# camera.net
KiCad netlist of a schematic drawn in Altium Designer
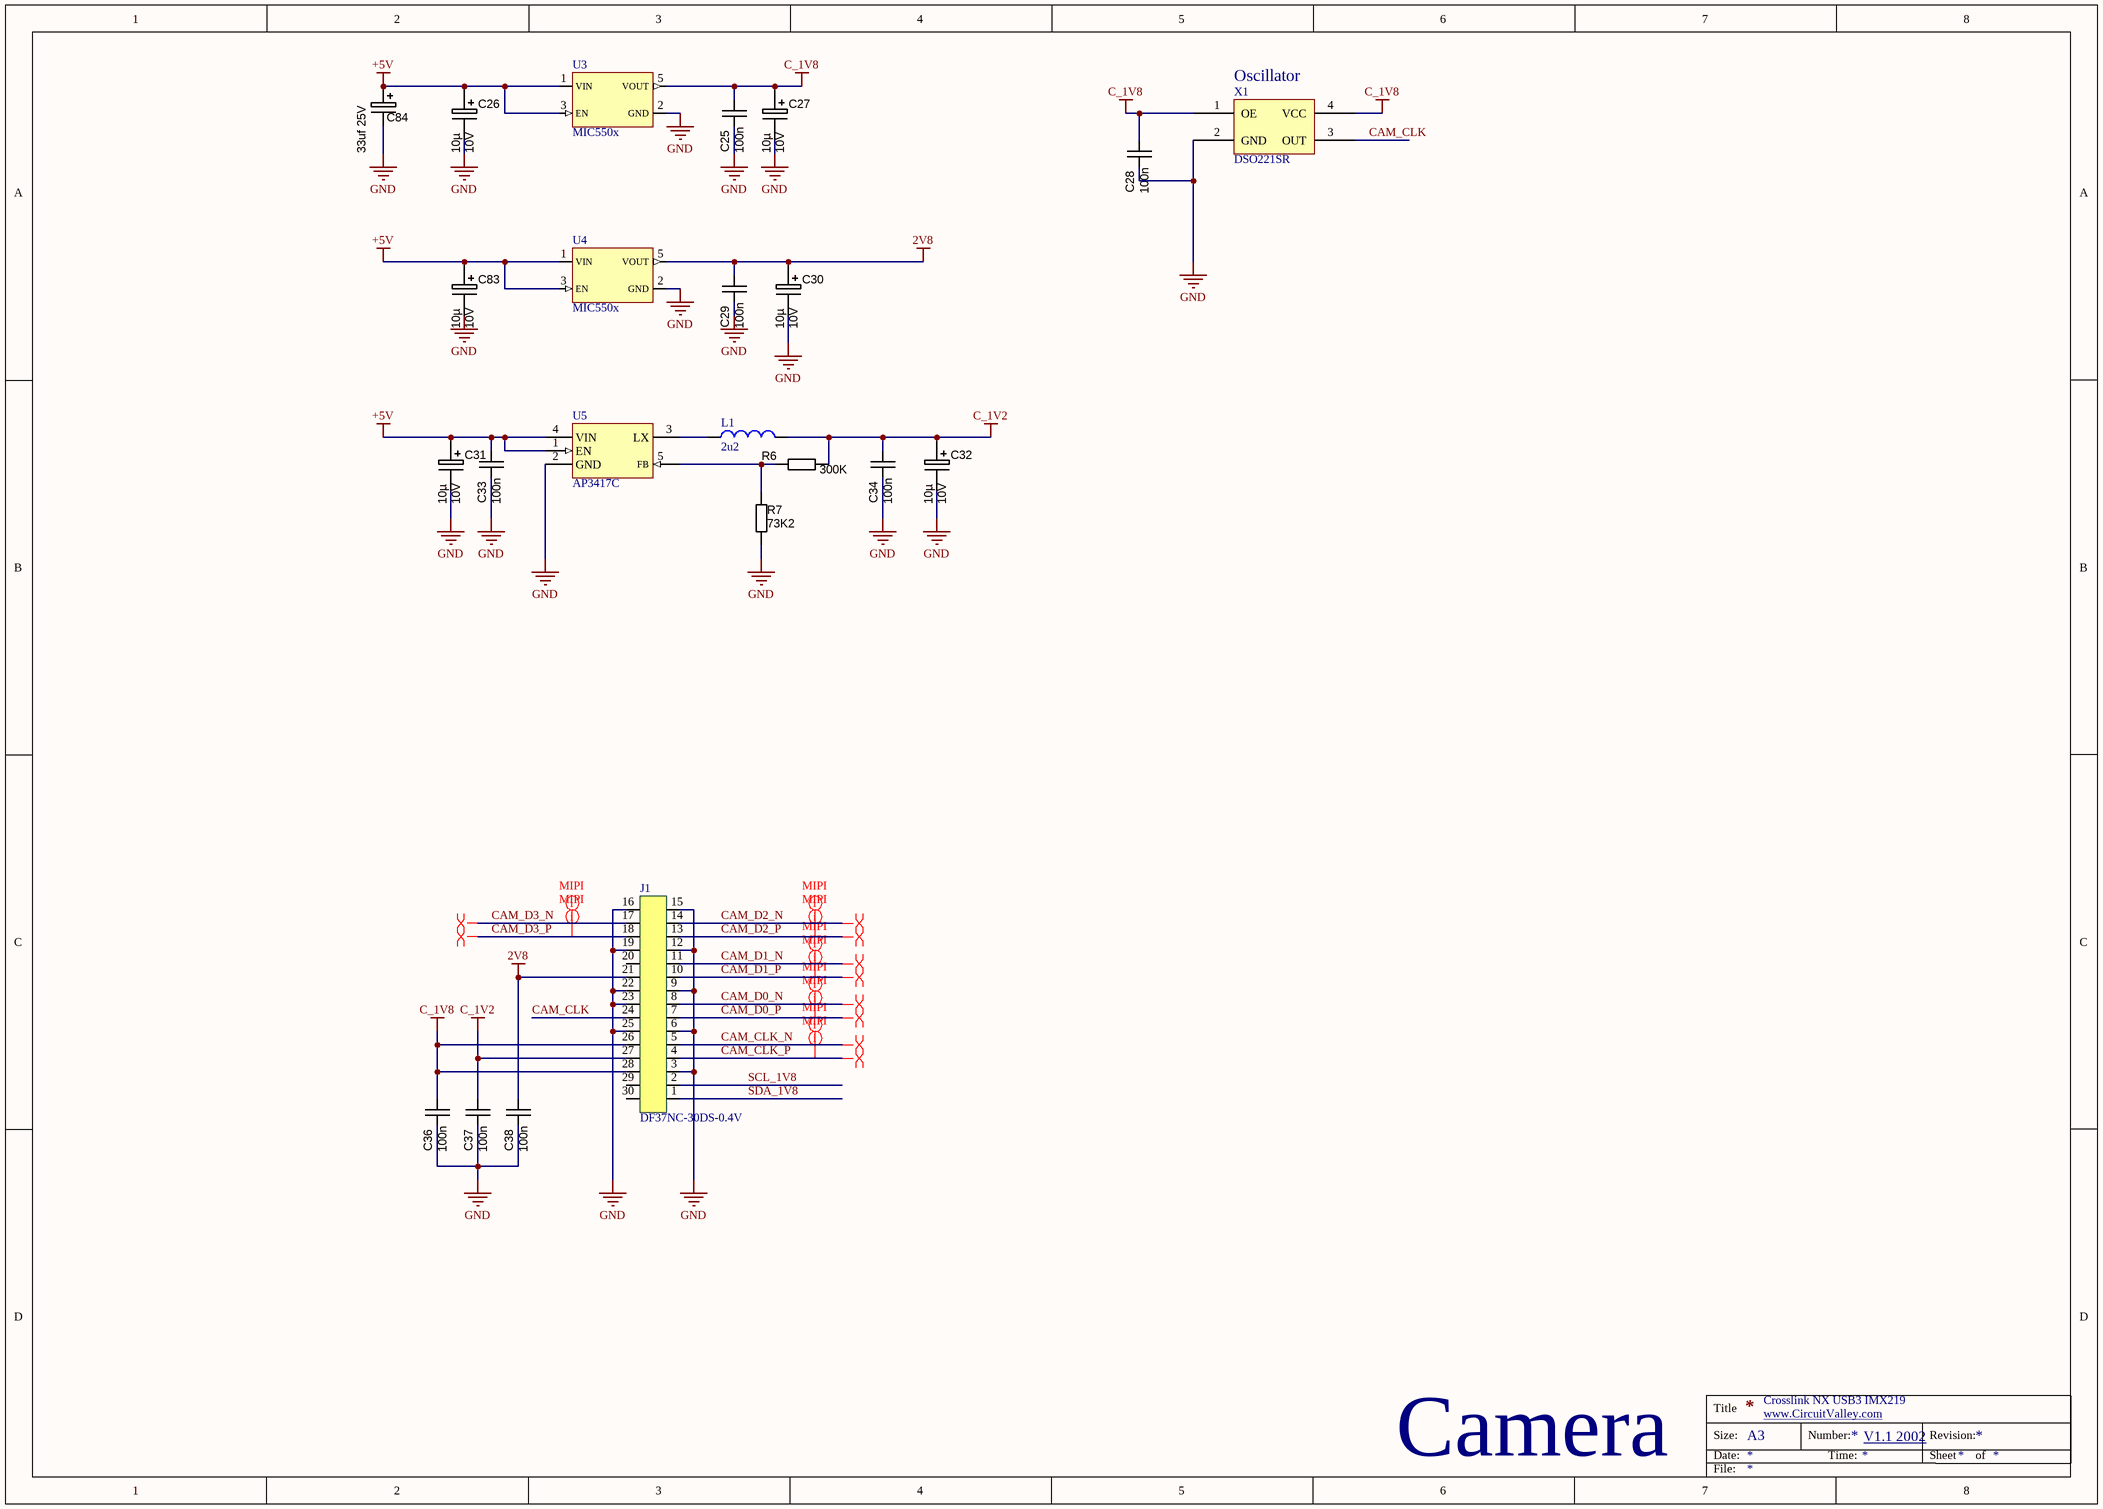
[diagram p0: camera.SchDoc]

(export (version "E")
  (design (tool "Eeschema 10.0.6"))
  (components
    (comp (ref "C25")
      (value "100n")
      (footprint "CAPC1608N")
      (description "Capacitor SMD Cer 10pF 5% 50V NP0 0603")
      (fields (field (name "TOLERANCE") "±5%") (field (name "PART") "C0603X104K5RAC"))
      (libsource (lib "PBL - Capacitors") (part "CAPC_10p_0603_NP0_1%_50V"))
    )
    (comp (ref "C26")
      (value "10µ")
      (footprint "CAPMP3528X210N")
      (description "Capacitor SMD Tantalum 47uF 20% 6.3V 1210")
      (fields (field (name "TOLERANCE") "±20%") (field (name "RATINGS") "10V"))
      (libsource (lib "PBL - Capacitors") (part "CAPT_47u_1210_6V3"))
    )
    (comp (ref "C27")
      (value "10µ")
      (footprint "CAPMP3528X210N")
      (description "Capacitor SMD Tantalum 47uF 20% 6.3V 1210")
      (fields (field (name "TOLERANCE") "±20%") (field (name "RATINGS") "10V"))
      (libsource (lib "PBL - Capacitors") (part "CAPT_47u_1210_6V3"))
    )
    (comp (ref "C28")
      (value "100n")
      (footprint "CAPC1608N")
      (description "Capacitor SMD Cer 10pF 5% 50V NP0 0603")
      (fields (field (name "TOLERANCE") "±5%") (field (name "PART") "C0603X104K5RAC"))
      (libsource (lib "PBL - Capacitors") (part "CAPC_10p_0603_NP0_1%_50V"))
    )
    (comp (ref "C29")
      (value "100n")
      (footprint "CAPC1608N")
      (description "Capacitor SMD Cer 10pF 5% 50V NP0 0603")
      (fields (field (name "TOLERANCE") "±5%") (field (name "PART") "C0603X104K5RAC"))
      (libsource (lib "PBL - Capacitors") (part "CAPC_10p_0603_NP0_1%_50V"))
    )
    (comp (ref "C30")
      (value "10µ")
      (footprint "CAPMP3528X210N")
      (description "Capacitor SMD Tantalum 47uF 20% 6.3V 1210")
      (fields (field (name "TOLERANCE") "±20%") (field (name "RATINGS") "10V"))
      (libsource (lib "PBL - Capacitors") (part "CAPT_47u_1210_6V3"))
    )
    (comp (ref "C31")
      (value "10µ")
      (footprint "CAPMP3528X210N")
      (description "Capacitor SMD Tantalum 47uF 20% 6.3V 1210")
      (fields (field (name "TOLERANCE") "±20%") (field (name "RATINGS") "10V"))
      (libsource (lib "PBL - Capacitors") (part "CAPT_47u_1210_6V3"))
    )
    (comp (ref "C32")
      (value "10µ")
      (footprint "CAPMP3528X210N")
      (description "Capacitor SMD Tantalum 47uF 20% 6.3V 1210")
      (fields (field (name "TOLERANCE") "±20%") (field (name "RATINGS") "10V"))
      (libsource (lib "PBL - Capacitors") (part "CAPT_47u_1210_6V3"))
    )
    (comp (ref "C33")
      (value "100n")
      (footprint "CAPC1608N")
      (description "Capacitor SMD Cer 10pF 5% 50V NP0 0603")
      (fields (field (name "TOLERANCE") "±5%") (field (name "PART") "C0603X104K5RAC"))
      (libsource (lib "PBL - Capacitors") (part "CAPC_10p_0603_NP0_1%_50V"))
    )
    (comp (ref "C34")
      (value "100n")
      (footprint "CAPC1608N")
      (description "Capacitor SMD Cer 10pF 5% 50V NP0 0603")
      (fields (field (name "TOLERANCE") "±5%") (field (name "PART") "C0603X104K5RAC"))
      (libsource (lib "PBL - Capacitors") (part "CAPC_10p_0603_NP0_1%_50V"))
    )
    (comp (ref "C36")
      (value "100n")
      (footprint "CAPC1608N")
      (description "Capacitor SMD Cer 10pF 5% 50V NP0 0603")
      (fields (field (name "TOLERANCE") "±5%") (field (name "PART") "C0603X104K5RAC"))
      (libsource (lib "PBL - Capacitors") (part "CAPC_10p_0603_NP0_1%_50V"))
    )
    (comp (ref "C37")
      (value "100n")
      (footprint "CAPC1608N")
      (description "Capacitor SMD Cer 10pF 5% 50V NP0 0603")
      (fields (field (name "TOLERANCE") "±5%") (field (name "PART") "C0603X104K5RAC"))
      (libsource (lib "PBL - Capacitors") (part "CAPC_10p_0603_NP0_1%_50V"))
    )
    (comp (ref "C38")
      (value "100n")
      (footprint "CAPC1608N")
      (description "Capacitor SMD Cer 10pF 5% 50V NP0 0603")
      (fields (field (name "TOLERANCE") "±5%") (field (name "PART") "C0603X104K5RAC"))
      (libsource (lib "PBL - Capacitors") (part "CAPC_10p_0603_NP0_1%_50V"))
    )
    (comp (ref "C83")
      (value "10µ")
      (footprint "CAPMP3528X210N")
      (description "Capacitor SMD Tantalum 47uF 20% 6.3V 1210")
      (fields (field (name "TOLERANCE") "±20%") (field (name "RATINGS") "10V"))
      (libsource (lib "PBL - Capacitors") (part "CAPT_47u_1210_6V3"))
    )
    (comp (ref "C84")
      (value "33uf 25V")
      (footprint "CAPMP7343X310N")
      (description "Capacitor SMD Tant 330uF 20% 6V3 2917")
      (fields
        (field (name "TOLERANCE") "±20%")
        (field (name "MANUFACTURER PART NUMBER") "T520D337M006ATE015")
      )
      (libsource (lib "PBL - Capacitors") (part "CAPT_330u_2917_6V3"))
    )
    (comp (ref "J1")
      (value "DF37NC-30DS-0.4V")
      (footprint "DF37NC-30DS-0.4V")
      (libsource (lib "Hiros") (part "30_Pin_Dual"))
    )
    (comp (ref "L1")
      (value "2u2")
      (footprint "TAIYO_NRS4018T2R2MDGJ")
      (fields (field (name "PARTNUMBER") "NRS4018T2R2MDGJ"))
      (libsource (lib "Inductor") (part "inductor_smd"))
    )
    (comp (ref "R6")
      (value "300K")
      (footprint "RESC1608N_ZERO")
      (description "Resistor SMD chip 0.0 Ohm 0.1W 0603")
      (fields (field (name "TOLERANCE") "±5%") (field (name "Comment") "Thick Film"))
      (libsource (lib "") (part "RES_0R_0603_1"))
    )
    (comp (ref "R7")
      (value "73K2")
      (footprint "RESC1608N_ZERO")
      (description "Resistor SMD chip 0.0 Ohm 0.1W 0603")
      (fields (field (name "TOLERANCE") "±5%") (field (name "Comment") "Thick Film"))
      (libsource (lib "PBL - Resistors") (part "RES_0R_0603"))
    )
    (comp (ref "U3") (value "MIC550x") (footprint "SOT23-5") (libsource (lib "cvlib") (part "MIC550x")))
    (comp (ref "U4") (value "MIC550x") (footprint "SOT23-5") (libsource (lib "cvlib") (part "MIC550x")))
    (comp (ref "U5") (value "AP3417C") (footprint "SOT23-5") (libsource (lib "cvlib") (part "AP3417C")))
    (comp (ref "X1")
      (value "DSO221SR")
      (footprint "Active Oscillator 2520")
      (description "Active Oscillator_2520")
      (libsource (lib "Crystal_and_oscillator") (part "Oscillator_2520"))
    )
  )
  (nets
    (net (code "1") (name "+5V") (class "Default")
      (node (ref "C26") (pin "1") (pintype "passive"))
      (node (ref "C31") (pin "1") (pintype "passive"))
      (node (ref "C33") (pin "2") (pintype "passive"))
      (node (ref "C83") (pin "1") (pintype "passive"))
      (node (ref "C84") (pin "1") (pintype "passive"))
      (node (ref "U3") (pin "1") (pinfunction "VIN_1") (pintype "power_in"))
      (node (ref "U3") (pin "3") (pinfunction "EN_3") (pintype "input"))
      (node (ref "U4") (pin "1") (pinfunction "VIN_1") (pintype "power_in"))
      (node (ref "U4") (pin "3") (pinfunction "EN_3") (pintype "input"))
      (node (ref "U5") (pin "1") (pinfunction "EN_1") (pintype "input"))
      (node (ref "U5") (pin "4") (pinfunction "VIN_4") (pintype "power_in"))
    )
    (net (code "2") (name "/CAM_CLK") (class "Default")
      (node (ref "J1") (pin "24") (pinfunction "24_24") (pintype "passive"))
      (node (ref "X1") (pin "3") (pinfunction "OUT_3") (pintype "passive"))
    )
    (net (code "3") (name "/CAM_CLK_N") (class "Default")
      (node (ref "J1") (pin "5") (pinfunction "5_5") (pintype "passive"))
    )
    (net (code "4") (name "/CAM_CLK_P") (class "Default")
      (node (ref "J1") (pin "4") (pinfunction "4_4") (pintype "passive"))
    )
    (net (code "5") (name "/CAM_D0_N") (class "Default")
      (node (ref "J1") (pin "8") (pinfunction "8_8") (pintype "passive"))
    )
    (net (code "6") (name "/CAM_D0_P") (class "Default")
      (node (ref "J1") (pin "7") (pinfunction "7_7") (pintype "passive"))
    )
    (net (code "7") (name "/CAM_D1_N") (class "Default")
      (node (ref "J1") (pin "11") (pinfunction "11_11") (pintype "passive"))
    )
    (net (code "8") (name "/CAM_D1_P") (class "Default")
      (node (ref "J1") (pin "10") (pinfunction "10_10") (pintype "passive"))
    )
    (net (code "9") (name "/CAM_D2_N") (class "Default")
      (node (ref "J1") (pin "14") (pinfunction "14_14") (pintype "passive"))
    )
    (net (code "10") (name "/CAM_D2_P") (class "Default")
      (node (ref "J1") (pin "13") (pinfunction "13_13") (pintype "passive"))
    )
    (net (code "11") (name "/CAM_D3_N") (class "Default")
      (node (ref "J1") (pin "17") (pinfunction "17_17") (pintype "passive"))
    )
    (net (code "12") (name "/CAM_D3_P") (class "Default")
      (node (ref "J1") (pin "18") (pinfunction "18_18") (pintype "passive"))
    )
    (net (code "13") (name "/SCL_1V8") (class "Default")
      (node (ref "J1") (pin "2") (pinfunction "2_2") (pintype "passive"))
    )
    (net (code "14") (name "/SDA_1V8") (class "Default")
      (node (ref "J1") (pin "1") (pinfunction "1_1") (pintype "passive"))
    )
    (net (code "15") (name "2V8") (class "Default")
      (node (ref "C29") (pin "2") (pintype "passive"))
      (node (ref "C30") (pin "1") (pintype "passive"))
      (node (ref "C38") (pin "2") (pintype "passive"))
      (node (ref "J1") (pin "21") (pinfunction "21_21") (pintype "passive"))
      (node (ref "U4") (pin "5") (pinfunction "VOUT_5") (pintype "output"))
    )
    (net (code "16") (name "C_1V2") (class "Default")
      (node (ref "C32") (pin "1") (pintype "passive"))
      (node (ref "C34") (pin "2") (pintype "passive"))
      (node (ref "C37") (pin "2") (pintype "passive"))
      (node (ref "J1") (pin "27") (pinfunction "27_27") (pintype "passive"))
      (node (ref "L1") (pin "2") (pinfunction "2_2") (pintype "passive"))
      (node (ref "R6") (pin "1") (pinfunction "1_1") (pintype "passive"))
    )
    (net (code "17") (name "C_1V8") (class "Default")
      (node (ref "C25") (pin "2") (pintype "passive"))
      (node (ref "C27") (pin "1") (pintype "passive"))
      (node (ref "C28") (pin "2") (pintype "passive"))
      (node (ref "C36") (pin "2") (pintype "passive"))
      (node (ref "J1") (pin "26") (pinfunction "26_26") (pintype "passive"))
      (node (ref "J1") (pin "28") (pinfunction "28_28") (pintype "passive"))
      (node (ref "U3") (pin "5") (pinfunction "VOUT_5") (pintype "output"))
      (node (ref "X1") (pin "1") (pinfunction "OE_1") (pintype "passive"))
      (node (ref "X1") (pin "4") (pinfunction "VCC_4") (pintype "passive"))
    )
    (net (code "18") (name "GND") (class "Default")
      (node (ref "C25") (pin "1") (pintype "passive"))
      (node (ref "C26") (pin "2") (pintype "passive"))
      (node (ref "C27") (pin "2") (pintype "passive"))
      (node (ref "C28") (pin "1") (pintype "passive"))
      (node (ref "C29") (pin "1") (pintype "passive"))
      (node (ref "C30") (pin "2") (pintype "passive"))
      (node (ref "C31") (pin "2") (pintype "passive"))
      (node (ref "C32") (pin "2") (pintype "passive"))
      (node (ref "C33") (pin "1") (pintype "passive"))
      (node (ref "C34") (pin "1") (pintype "passive"))
      (node (ref "C36") (pin "1") (pintype "passive"))
      (node (ref "C37") (pin "1") (pintype "passive"))
      (node (ref "C38") (pin "1") (pintype "passive"))
      (node (ref "C83") (pin "2") (pintype "passive"))
      (node (ref "C84") (pin "2") (pintype "passive"))
      (node (ref "J1") (pin "12") (pinfunction "12_12") (pintype "passive"))
      (node (ref "J1") (pin "15") (pinfunction "15_15") (pintype "passive"))
      (node (ref "J1") (pin "16") (pinfunction "16_16") (pintype "passive"))
      (node (ref "J1") (pin "19") (pinfunction "19_19") (pintype "passive"))
      (node (ref "J1") (pin "22") (pinfunction "22_22") (pintype "passive"))
      (node (ref "J1") (pin "23") (pinfunction "23_23") (pintype "passive"))
      (node (ref "J1") (pin "25") (pinfunction "25_25") (pintype "passive"))
      (node (ref "J1") (pin "3") (pinfunction "3_3") (pintype "passive"))
      (node (ref "J1") (pin "6") (pinfunction "6_6") (pintype "passive"))
      (node (ref "J1") (pin "9") (pinfunction "9_9") (pintype "passive"))
      (node (ref "R7") (pin "2") (pinfunction "2_2") (pintype "passive"))
      (node (ref "U3") (pin "2") (pinfunction "GND_2") (pintype "power_in"))
      (node (ref "U4") (pin "2") (pinfunction "GND_2") (pintype "power_in"))
      (node (ref "U5") (pin "2") (pinfunction "GND_2") (pintype "power_in"))
      (node (ref "X1") (pin "2") (pinfunction "GND_2") (pintype "passive"))
    )
    (net (code "19") (name "Net-(U5-FB)") (class "Default")
      (node (ref "R6") (pin "2") (pinfunction "2_2") (pintype "passive"))
      (node (ref "R7") (pin "1") (pinfunction "1_1") (pintype "passive"))
      (node (ref "U5") (pin "5") (pinfunction "FB_5") (pintype "input"))
    )
    (net (code "20") (name "Net-(U5-LX)") (class "Default")
      (node (ref "L1") (pin "1") (pinfunction "1_1") (pintype "passive"))
      (node (ref "U5") (pin "3") (pinfunction "LX_3") (pintype "passive"))
    )
    (net (code "21") (name "unconnected-(J1-Pad20)") (class "Default")
      (node (ref "J1") (pin "20") (pinfunction "20_20") (pintype "passive"))
    )
    (net (code "22") (name "unconnected-(J1-Pad29)") (class "Default")
      (node (ref "J1") (pin "29") (pinfunction "29_29") (pintype "passive"))
    )
    (net (code "23") (name "unconnected-(J1-Pad30)") (class "Default")
      (node (ref "J1") (pin "30") (pinfunction "30_30") (pintype "passive"))
    )
  )
)
